# Sensor_Brushless_Driver_V1_01.net
KiCad netlist of a schematic drawn in Altium Designer
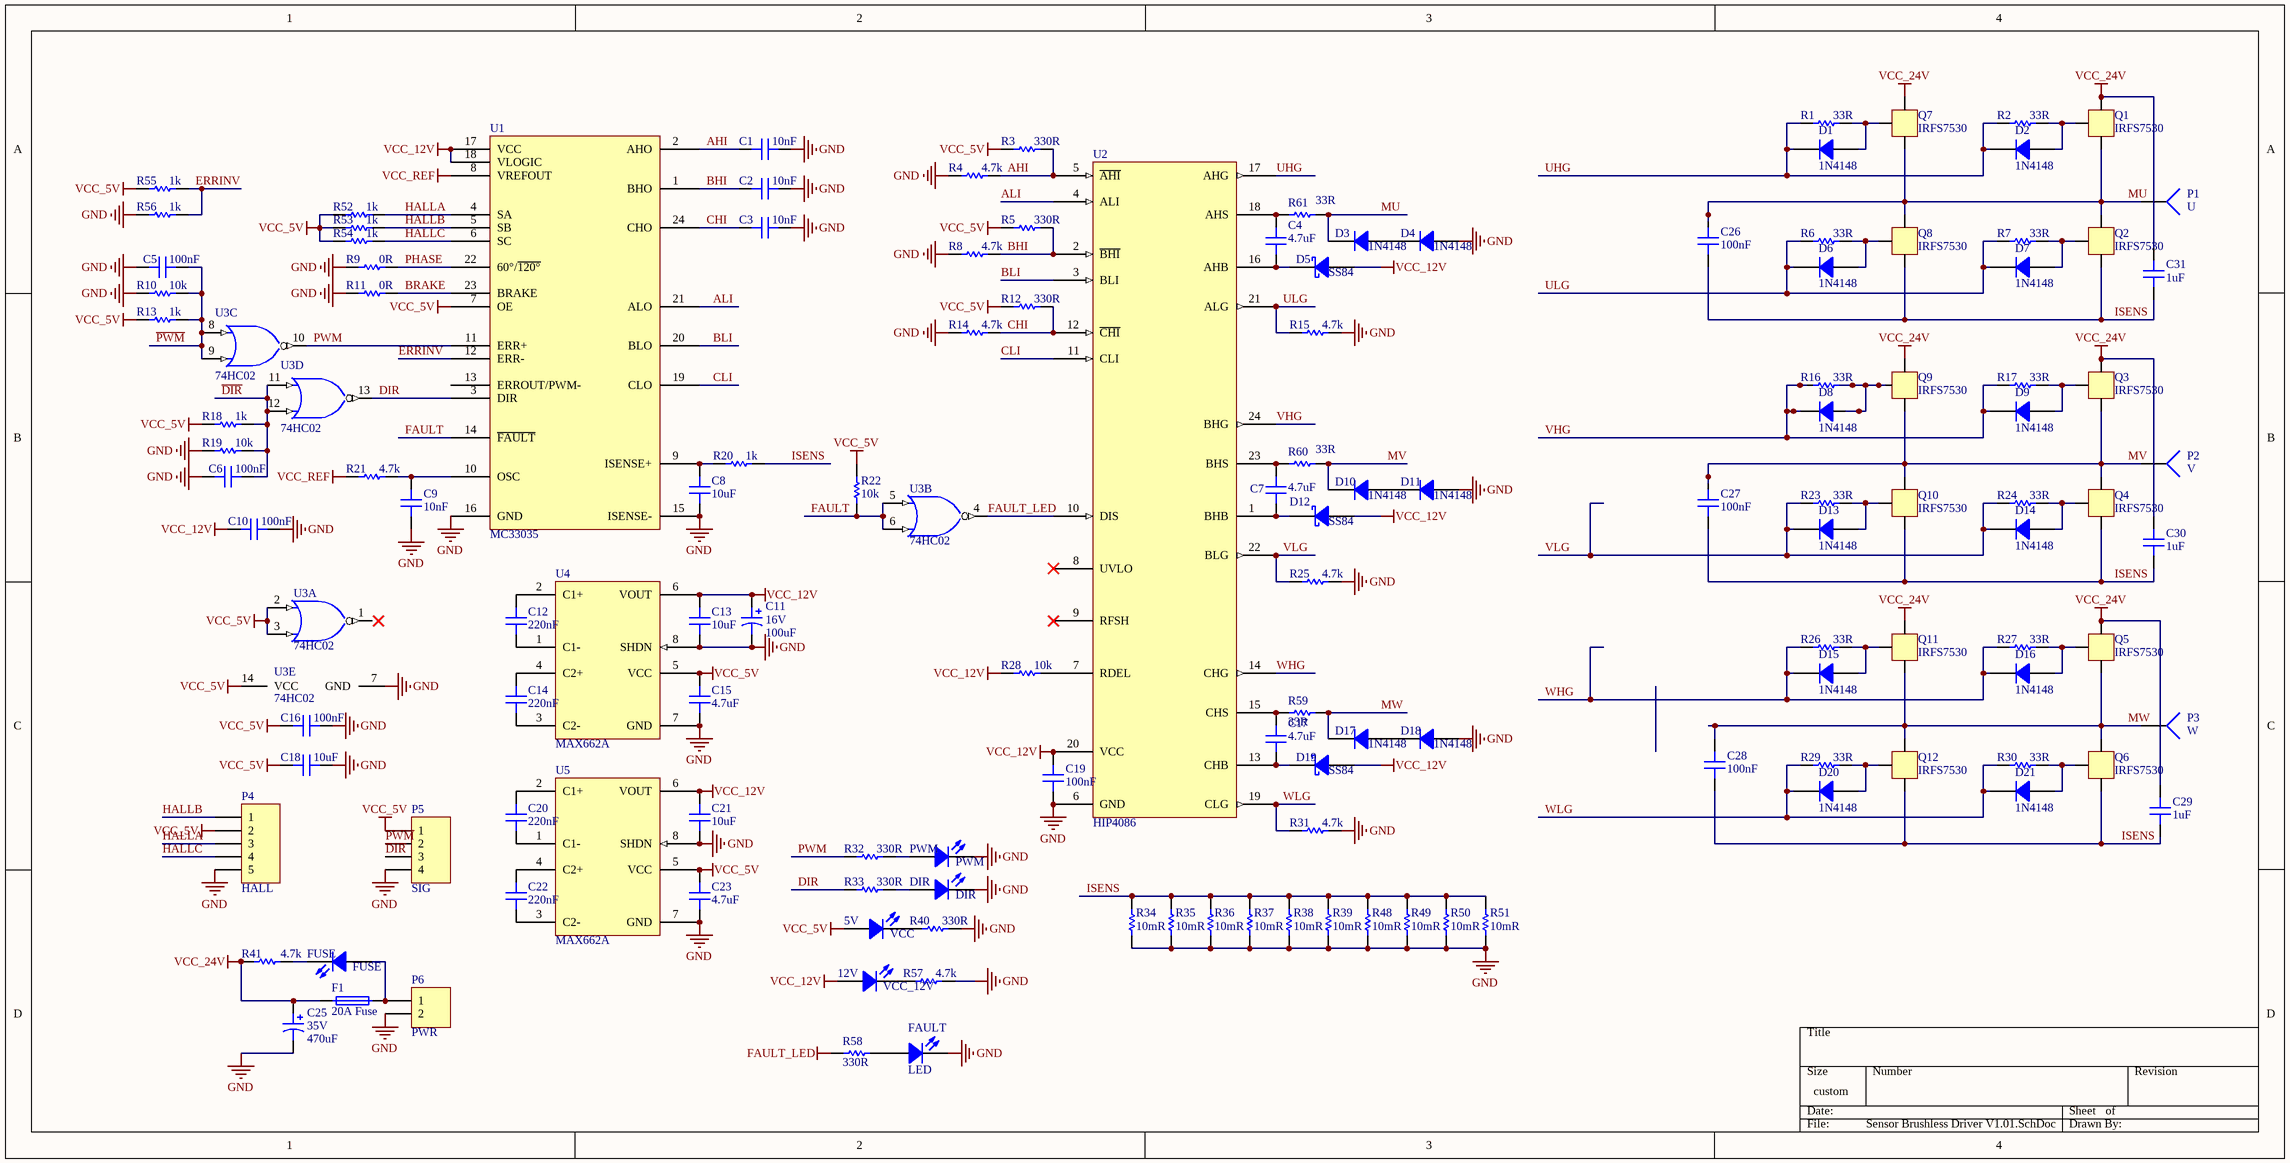
[diagram p0: Sensor Brushless Driver V1.01.SchDoc]

(export (version "E")
  (design (tool "Eeschema 10.0.6"))
  (components
    (comp (ref "5V")
      (value "VCC")
      (footprint "D0805")
      (description "Typical RED GaAs LED")
      (libsource (lib "Robocon_BJT") (part "LED"))
    )
    (comp (ref "12V")
      (value "VCC_12V")
      (footprint "D0805")
      (description "Typical RED GaAs LED")
      (libsource (lib "Robocon_BJT") (part "LED"))
    )
    (comp (ref "C1")
      (value "10nF")
      (footprint "CC2012-0805")
      (description "Capacitor (Semiconductor SIM Model)")
      (libsource (lib "Robocon_RCL") (part "Cap Semi"))
    )
    (comp (ref "C2")
      (value "10nF")
      (footprint "CC2012-0805")
      (description "Capacitor (Semiconductor SIM Model)")
      (libsource (lib "Robocon_RCL") (part "Cap Semi"))
    )
    (comp (ref "C3")
      (value "10nF")
      (footprint "CC2012-0805")
      (description "Capacitor (Semiconductor SIM Model)")
      (libsource (lib "Robocon_RCL") (part "Cap Semi"))
    )
    (comp (ref "C4")
      (value "4.7uF")
      (footprint "CC2012-0805")
      (description "Capacitor (Semiconductor SIM Model)")
      (libsource (lib "Robocon_RCL") (part "Cap Semi"))
    )
    (comp (ref "C5")
      (value "100nF")
      (footprint "CC2012-0805")
      (description "Capacitor (Semiconductor SIM Model)")
      (libsource (lib "Robocon_RCL") (part "Cap Semi"))
    )
    (comp (ref "C6")
      (value "100nF")
      (footprint "CC2012-0805")
      (description "Capacitor (Semiconductor SIM Model)")
      (libsource (lib "Robocon_RCL") (part "Cap Semi"))
    )
    (comp (ref "C7")
      (value "4.7uF")
      (footprint "CC2012-0805")
      (description "Capacitor (Semiconductor SIM Model)")
      (libsource (lib "Robocon_RCL") (part "Cap Semi"))
    )
    (comp (ref "C8")
      (value "10uF")
      (footprint "CC3216-1206")
      (description "Capacitor (Semiconductor SIM Model)")
      (libsource (lib "Robocon_RCL") (part "Cap Semi"))
    )
    (comp (ref "C9")
      (value "10nF")
      (footprint "CC2012-0805")
      (description "Capacitor (Semiconductor SIM Model)")
      (libsource (lib "Robocon_RCL") (part "Cap Semi"))
    )
    (comp (ref "C10")
      (value "100nF")
      (footprint "CC2012-0805")
      (description "Capacitor (Semiconductor SIM Model)")
      (libsource (lib "Robocon_RCL") (part "Cap Semi"))
    )
    (comp (ref "C11")
      (value "100uF")
      (footprint "EIA7343")
      (description "Polarized Capacitor (Axial)")
      (fields (field (name "VOLTAGE") "16V"))
      (libsource (lib "Robocon_RCL") (part "Cap Pol SMD"))
    )
    (comp (ref "C12")
      (value "220nF")
      (footprint "CC2012-0805")
      (description "Capacitor (Semiconductor SIM Model)")
      (libsource (lib "Robocon_RCL") (part "Cap Semi"))
    )
    (comp (ref "C13")
      (value "10uF")
      (footprint "CC3216-1206")
      (description "Capacitor (Semiconductor SIM Model)")
      (libsource (lib "Robocon_RCL") (part "Cap Semi"))
    )
    (comp (ref "C14")
      (value "220nF")
      (footprint "CC2012-0805")
      (description "Capacitor (Semiconductor SIM Model)")
      (libsource (lib "Robocon_RCL") (part "Cap Semi"))
    )
    (comp (ref "C15")
      (value "4.7uF")
      (footprint "CC2012-0805")
      (description "Capacitor (Semiconductor SIM Model)")
      (libsource (lib "Robocon_RCL") (part "Cap Semi"))
    )
    (comp (ref "C16")
      (value "100nF")
      (footprint "CC2012-0805")
      (description "Capacitor (Semiconductor SIM Model)")
      (libsource (lib "Robocon_RCL") (part "Cap Semi"))
    )
    (comp (ref "C17")
      (value "4.7uF")
      (footprint "CC2012-0805")
      (description "Capacitor (Semiconductor SIM Model)")
      (libsource (lib "Robocon_RCL") (part "Cap Semi"))
    )
    (comp (ref "C18")
      (value "10uF")
      (footprint "CC3216-1206")
      (description "Capacitor (Semiconductor SIM Model)")
      (libsource (lib "Robocon_RCL") (part "Cap Semi"))
    )
    (comp (ref "C19")
      (value "100nF")
      (footprint "CC2012-0805")
      (description "Capacitor (Semiconductor SIM Model)")
      (libsource (lib "Robocon_RCL") (part "Cap Semi"))
    )
    (comp (ref "C20")
      (value "220nF")
      (footprint "CC2012-0805")
      (description "Capacitor (Semiconductor SIM Model)")
      (libsource (lib "Robocon_RCL") (part "Cap Semi"))
    )
    (comp (ref "C21")
      (value "10uF")
      (footprint "CC3216-1206")
      (description "Capacitor (Semiconductor SIM Model)")
      (libsource (lib "Robocon_RCL") (part "Cap Semi"))
    )
    (comp (ref "C22")
      (value "220nF")
      (footprint "CC2012-0805")
      (description "Capacitor (Semiconductor SIM Model)")
      (libsource (lib "Robocon_RCL") (part "Cap Semi"))
    )
    (comp (ref "C23")
      (value "4.7uF")
      (footprint "CC2012-0805")
      (description "Capacitor (Semiconductor SIM Model)")
      (libsource (lib "Robocon_RCL") (part "Cap Semi"))
    )
    (comp (ref "C25")
      (value "470uF")
      (footprint "CAP10x12")
      (description "Polarized Capacitor (Radial)")
      (fields (field (name "VOLTAGE") "35V"))
      (libsource (lib "Robocon_RCL") (part "Cap Pol DIP"))
    )
    (comp (ref "C26")
      (value "100nF")
      (footprint "CC2012-0805")
      (description "Capacitor (Semiconductor SIM Model)")
      (libsource (lib "Robocon_RCL") (part "Cap Semi"))
    )
    (comp (ref "C27")
      (value "100nF")
      (footprint "CC2012-0805")
      (description "Capacitor (Semiconductor SIM Model)")
      (libsource (lib "Robocon_RCL") (part "Cap Semi"))
    )
    (comp (ref "C28")
      (value "100nF")
      (footprint "CC2012-0805")
      (description "Capacitor (Semiconductor SIM Model)")
      (libsource (lib "Robocon_RCL") (part "Cap Semi"))
    )
    (comp (ref "C29")
      (value "1uF")
      (footprint "CC2012-0805")
      (description "Capacitor (Semiconductor SIM Model)")
      (libsource (lib "Robocon_RCL") (part "Cap Semi"))
    )
    (comp (ref "C30")
      (value "1uF")
      (footprint "CC2012-0805")
      (description "Capacitor (Semiconductor SIM Model)")
      (libsource (lib "Robocon_RCL") (part "Cap Semi"))
    )
    (comp (ref "C31")
      (value "1uF")
      (footprint "CC2012-0805")
      (description "Capacitor (Semiconductor SIM Model)")
      (libsource (lib "Robocon_RCL") (part "Cap Semi"))
    )
    (comp (ref "D1")
      (value "1N4148")
      (footprint "SOD-80")
      (description "General Purpose Diode")
      (libsource (lib "Robocon_BJT") (part "D General"))
    )
    (comp (ref "D2")
      (value "1N4148")
      (footprint "SOD-80")
      (description "General Purpose Diode")
      (libsource (lib "Robocon_BJT") (part "D General"))
    )
    (comp (ref "D3")
      (value "1N4148")
      (footprint "SOD-80")
      (description "General Purpose Diode")
      (libsource (lib "Robocon_BJT") (part "D General"))
    )
    (comp (ref "D4")
      (value "1N4148")
      (footprint "SOD-80")
      (description "General Purpose Diode")
      (libsource (lib "Robocon_BJT") (part "D General"))
    )
    (comp (ref "D5")
      (value "SS84")
      (footprint "SMC")
      (description "Schottky Diode")
      (libsource (lib "Robocon_BJT") (part "D Schottky"))
    )
    (comp (ref "D6")
      (value "1N4148")
      (footprint "SOD-80")
      (description "General Purpose Diode")
      (libsource (lib "Robocon_BJT") (part "D General"))
    )
    (comp (ref "D7")
      (value "1N4148")
      (footprint "SOD-80")
      (description "General Purpose Diode")
      (libsource (lib "Robocon_BJT") (part "D General"))
    )
    (comp (ref "D8")
      (value "1N4148")
      (footprint "SOD-80")
      (description "General Purpose Diode")
      (libsource (lib "Robocon_BJT") (part "D General"))
    )
    (comp (ref "D9")
      (value "1N4148")
      (footprint "SOD-80")
      (description "General Purpose Diode")
      (libsource (lib "Robocon_BJT") (part "D General"))
    )
    (comp (ref "D10")
      (value "1N4148")
      (footprint "SOD-80")
      (description "General Purpose Diode")
      (libsource (lib "Robocon_BJT") (part "D General"))
    )
    (comp (ref "D11")
      (value "1N4148")
      (footprint "SOD-80")
      (description "General Purpose Diode")
      (libsource (lib "Robocon_BJT") (part "D General"))
    )
    (comp (ref "D12")
      (value "SS84")
      (footprint "SMC")
      (description "Schottky Diode")
      (libsource (lib "Robocon_BJT") (part "D Schottky"))
    )
    (comp (ref "D13")
      (value "1N4148")
      (footprint "SOD-80")
      (description "General Purpose Diode")
      (libsource (lib "Robocon_BJT") (part "D General"))
    )
    (comp (ref "D14")
      (value "1N4148")
      (footprint "SOD-80")
      (description "General Purpose Diode")
      (libsource (lib "Robocon_BJT") (part "D General"))
    )
    (comp (ref "D15")
      (value "1N4148")
      (footprint "SOD-80")
      (description "General Purpose Diode")
      (libsource (lib "Robocon_BJT") (part "D General"))
    )
    (comp (ref "D16")
      (value "1N4148")
      (footprint "SOD-80")
      (description "General Purpose Diode")
      (libsource (lib "Robocon_BJT") (part "D General"))
    )
    (comp (ref "D17")
      (value "1N4148")
      (footprint "SOD-80")
      (description "General Purpose Diode")
      (libsource (lib "Robocon_BJT") (part "D General"))
    )
    (comp (ref "D18")
      (value "1N4148")
      (footprint "SOD-80")
      (description "General Purpose Diode")
      (libsource (lib "Robocon_BJT") (part "D General"))
    )
    (comp (ref "D19")
      (value "SS84")
      (footprint "SMC")
      (description "Schottky Diode")
      (libsource (lib "Robocon_BJT") (part "D Schottky"))
    )
    (comp (ref "D20")
      (value "1N4148")
      (footprint "SOD-80")
      (description "General Purpose Diode")
      (libsource (lib "Robocon_BJT") (part "D General"))
    )
    (comp (ref "D21")
      (value "1N4148")
      (footprint "SOD-80")
      (description "General Purpose Diode")
      (libsource (lib "Robocon_BJT") (part "D General"))
    )
    (comp (ref "DIR")
      (value "DIR")
      (footprint "D0805")
      (description "Typical RED GaAs LED")
      (libsource (lib "Robocon_BJT") (part "LED"))
    )
    (comp (ref "F1")
      (value "20A Fuse")
      (footprint "Robocon_RCL:FUSE SOCKET")
      (description "Fuse")
      (libsource (lib "Robocon_RCL") (part "Fuse"))
    )
    (comp (ref "FAULT")
      (value "LED")
      (footprint "D0805")
      (description "Typical RED GaAs LED")
      (libsource (lib "Robocon_BJT") (part "LED"))
    )
    (comp (ref "FUSE")
      (value "FUSE")
      (footprint "D0805")
      (description "Typical RED GaAs LED")
      (libsource (lib "Robocon_BJT") (part "LED"))
    )
    (comp (ref "P1")
      (value "U")
      (footprint "2.5X4_WIRE_PAD")
      (description "Socket")
      (libsource (lib "Robocon_connectors") (part "Socket"))
    )
    (comp (ref "P2")
      (value "V")
      (footprint "2.5X4_WIRE_PAD")
      (description "Socket")
      (libsource (lib "Robocon_connectors") (part "Socket"))
    )
    (comp (ref "P3")
      (value "W")
      (footprint "2.5X4_WIRE_PAD")
      (description "Socket")
      (libsource (lib "Robocon_connectors") (part "Socket"))
    )
    (comp (ref "P4")
      (value "HALL")
      (footprint "LOCKEDHDR-5W")
      (description "Header, 5-Pin")
      (libsource (lib "Robocon_connectors") (part "Header 5"))
    )
    (comp (ref "P5")
      (value "SIG")
      (footprint "LOCKEDHDR-4W")
      (description "Header, 4-Pin")
      (libsource (lib "Robocon_connectors") (part "Header 4"))
    )
    (comp (ref "P6")
      (value "PWR")
      (footprint "xt60(m)")
      (description "Header, 2-Pin")
      (libsource (lib "Robocon_connectors") (part "Header 2"))
    )
    (comp (ref "PWM")
      (value "PWM")
      (footprint "D0805")
      (description "Typical RED GaAs LED")
      (libsource (lib "Robocon_BJT") (part "LED"))
    )
    (comp (ref "Q1") (value "IRFS7530") (footprint "D2k 7 pin") (libsource (lib "Schlib1") (part "D2k 7")))
    (comp (ref "Q2") (value "IRFS7530") (footprint "D2k 7 pin") (libsource (lib "Schlib1") (part "D2k 7")))
    (comp (ref "Q3") (value "IRFS7530") (footprint "D2k 7 pin") (libsource (lib "Schlib1") (part "D2k 7")))
    (comp (ref "Q4") (value "IRFS7530") (footprint "D2k 7 pin") (libsource (lib "Schlib1") (part "D2k 7")))
    (comp (ref "Q5") (value "IRFS7530") (footprint "D2k 7 pin") (libsource (lib "Schlib1") (part "D2k 7")))
    (comp (ref "Q6") (value "IRFS7530") (footprint "D2k 7 pin") (libsource (lib "Schlib1") (part "D2k 7")))
    (comp (ref "Q7") (value "IRFS7530") (footprint "D2k 7 pin") (libsource (lib "Schlib1") (part "D2k 7")))
    (comp (ref "Q8") (value "IRFS7530") (footprint "D2k 7 pin") (libsource (lib "Schlib1") (part "D2k 7")))
    (comp (ref "Q9") (value "IRFS7530") (footprint "D2k 7 pin") (libsource (lib "Schlib1") (part "D2k 7")))
    (comp (ref "Q10") (value "IRFS7530") (footprint "D2k 7 pin") (libsource (lib "Schlib1") (part "D2k 7")))
    (comp (ref "Q11") (value "IRFS7530") (footprint "D2k 7 pin") (libsource (lib "Schlib1") (part "D2k 7")))
    (comp (ref "Q12") (value "IRFS7530") (footprint "D2k 7 pin") (libsource (lib "Schlib1") (part "D2k 7")))
    (comp (ref "R1")
      (value "33R")
      (footprint "CR2012-0805")
      (description "Semiconductor Resistor")
      (libsource (lib "Robocon_RCL") (part "Res Semi"))
    )
    (comp (ref "R2")
      (value "33R")
      (footprint "CR2012-0805")
      (description "Semiconductor Resistor")
      (libsource (lib "Robocon_RCL") (part "Res Semi"))
    )
    (comp (ref "R3")
      (value "330R")
      (footprint "CR2012-0805")
      (description "Semiconductor Resistor")
      (libsource (lib "Robocon_RCL") (part "Res Semi"))
    )
    (comp (ref "R4")
      (value "4.7k")
      (footprint "CR2012-0805")
      (description "Semiconductor Resistor")
      (libsource (lib "Robocon_RCL") (part "Res Semi"))
    )
    (comp (ref "R5")
      (value "330R")
      (footprint "CR2012-0805")
      (description "Semiconductor Resistor")
      (libsource (lib "Robocon_RCL") (part "Res Semi"))
    )
    (comp (ref "R6")
      (value "33R")
      (footprint "CR2012-0805")
      (description "Semiconductor Resistor")
      (libsource (lib "Robocon_RCL") (part "Res Semi"))
    )
    (comp (ref "R7")
      (value "33R")
      (footprint "CR2012-0805")
      (description "Semiconductor Resistor")
      (libsource (lib "Robocon_RCL") (part "Res Semi"))
    )
    (comp (ref "R8")
      (value "4.7k")
      (footprint "CR2012-0805")
      (description "Semiconductor Resistor")
      (libsource (lib "Robocon_RCL") (part "Res Semi"))
    )
    (comp (ref "R9")
      (value "0R")
      (footprint "CR2012-0805")
      (description "Semiconductor Resistor")
      (libsource (lib "Robocon_RCL") (part "Res Semi"))
    )
    (comp (ref "R10")
      (value "10k")
      (footprint "CR2012-0805")
      (description "Semiconductor Resistor")
      (libsource (lib "Robocon_RCL") (part "Res Semi"))
    )
    (comp (ref "R11")
      (value "0R")
      (footprint "CR2012-0805")
      (description "Semiconductor Resistor")
      (libsource (lib "Robocon_RCL") (part "Res Semi"))
    )
    (comp (ref "R12")
      (value "330R")
      (footprint "CR2012-0805")
      (description "Semiconductor Resistor")
      (libsource (lib "Robocon_RCL") (part "Res Semi"))
    )
    (comp (ref "R13")
      (value "1k")
      (footprint "CR2012-0805")
      (description "Semiconductor Resistor")
      (libsource (lib "Robocon_RCL") (part "Res Semi"))
    )
    (comp (ref "R14")
      (value "4.7k")
      (footprint "CR2012-0805")
      (description "Semiconductor Resistor")
      (libsource (lib "Robocon_RCL") (part "Res Semi"))
    )
    (comp (ref "R15")
      (value "4.7k")
      (footprint "CR2012-0805")
      (description "Semiconductor Resistor")
      (libsource (lib "Robocon_RCL") (part "Res Semi"))
    )
    (comp (ref "R16")
      (value "33R")
      (footprint "CR2012-0805")
      (description "Semiconductor Resistor")
      (libsource (lib "Robocon_RCL") (part "Res Semi"))
    )
    (comp (ref "R17")
      (value "33R")
      (footprint "CR2012-0805")
      (description "Semiconductor Resistor")
      (libsource (lib "Robocon_RCL") (part "Res Semi"))
    )
    (comp (ref "R18")
      (value "1k")
      (footprint "CR2012-0805")
      (description "Semiconductor Resistor")
      (libsource (lib "Robocon_RCL") (part "Res Semi"))
    )
    (comp (ref "R19")
      (value "10k")
      (footprint "CR2012-0805")
      (description "Semiconductor Resistor")
      (libsource (lib "Robocon_RCL") (part "Res Semi"))
    )
    (comp (ref "R20")
      (value "1k")
      (footprint "CR2012-0805")
      (description "Semiconductor Resistor")
      (libsource (lib "Robocon_RCL") (part "Res Semi"))
    )
    (comp (ref "R21")
      (value "4.7k")
      (footprint "CR2012-0805")
      (description "Semiconductor Resistor")
      (libsource (lib "Robocon_RCL") (part "Res Semi"))
    )
    (comp (ref "R22")
      (value "10k")
      (footprint "CR2012-0805")
      (description "Semiconductor Resistor")
      (libsource (lib "Robocon_RCL") (part "Res Semi"))
    )
    (comp (ref "R23")
      (value "33R")
      (footprint "CR2012-0805")
      (description "Semiconductor Resistor")
      (libsource (lib "Robocon_RCL") (part "Res Semi"))
    )
    (comp (ref "R24")
      (value "33R")
      (footprint "CR2012-0805")
      (description "Semiconductor Resistor")
      (libsource (lib "Robocon_RCL") (part "Res Semi"))
    )
    (comp (ref "R25")
      (value "4.7k")
      (footprint "CR2012-0805")
      (description "Semiconductor Resistor")
      (libsource (lib "Robocon_RCL") (part "Res Semi"))
    )
    (comp (ref "R26")
      (value "33R")
      (footprint "CR2012-0805")
      (description "Semiconductor Resistor")
      (libsource (lib "Robocon_RCL") (part "Res Semi"))
    )
    (comp (ref "R27")
      (value "33R")
      (footprint "CR2012-0805")
      (description "Semiconductor Resistor")
      (libsource (lib "Robocon_RCL") (part "Res Semi"))
    )
    (comp (ref "R28")
      (value "10k")
      (footprint "CR2012-0805")
      (description "Semiconductor Resistor")
      (libsource (lib "Robocon_RCL") (part "Res Semi"))
    )
    (comp (ref "R29")
      (value "33R")
      (footprint "CR2012-0805")
      (description "Semiconductor Resistor")
      (libsource (lib "Robocon_RCL") (part "Res Semi"))
    )
    (comp (ref "R30")
      (value "33R")
      (footprint "CR2012-0805")
      (description "Semiconductor Resistor")
      (libsource (lib "Robocon_RCL") (part "Res Semi"))
    )
    (comp (ref "R31")
      (value "4.7k")
      (footprint "CR2012-0805")
      (description "Semiconductor Resistor")
      (libsource (lib "Robocon_RCL") (part "Res Semi"))
    )
    (comp (ref "R32")
      (value "330R")
      (footprint "CR2012-0805")
      (description "Semiconductor Resistor")
      (libsource (lib "Robocon_RCL") (part "Res Semi"))
    )
    (comp (ref "R33")
      (value "330R")
      (footprint "CR2012-0805")
      (description "Semiconductor Resistor")
      (libsource (lib "Robocon_RCL") (part "Res Semi"))
    )
    (comp (ref "R34")
      (value "10mR")
      (footprint "CR6332-2512")
      (description "Semiconductor Resistor")
      (libsource (lib "Robocon_RCL") (part "Res Semi"))
    )
    (comp (ref "R35")
      (value "10mR")
      (footprint "CR6332-2512")
      (description "Semiconductor Resistor")
      (libsource (lib "Robocon_RCL") (part "Res Semi"))
    )
    (comp (ref "R36")
      (value "10mR")
      (footprint "CR6332-2512")
      (description "Semiconductor Resistor")
      (libsource (lib "Robocon_RCL") (part "Res Semi"))
    )
    (comp (ref "R37")
      (value "10mR")
      (footprint "CR6332-2512")
      (description "Semiconductor Resistor")
      (libsource (lib "Robocon_RCL") (part "Res Semi"))
    )
    (comp (ref "R38")
      (value "10mR")
      (footprint "CR6332-2512")
      (description "Semiconductor Resistor")
      (libsource (lib "Robocon_RCL") (part "Res Semi"))
    )
    (comp (ref "R39")
      (value "10mR")
      (footprint "CR6332-2512")
      (description "Semiconductor Resistor")
      (libsource (lib "Robocon_RCL") (part "Res Semi"))
    )
    (comp (ref "R40")
      (value "330R")
      (footprint "CR2012-0805")
      (description "Semiconductor Resistor")
      (libsource (lib "Robocon_RCL") (part "Res Semi"))
    )
    (comp (ref "R41")
      (value "4.7k")
      (footprint "CR2012-0805")
      (description "Semiconductor Resistor")
      (libsource (lib "Robocon_RCL") (part "Res Semi"))
    )
    (comp (ref "R48")
      (value "10mR")
      (footprint "CR6332-2512")
      (description "Semiconductor Resistor")
      (libsource (lib "Robocon_RCL") (part "Res Semi"))
    )
    (comp (ref "R49")
      (value "10mR")
      (footprint "CR6332-2512")
      (description "Semiconductor Resistor")
      (libsource (lib "Robocon_RCL") (part "Res Semi"))
    )
    (comp (ref "R50")
      (value "10mR")
      (footprint "CR6332-2512")
      (description "Semiconductor Resistor")
      (libsource (lib "Robocon_RCL") (part "Res Semi"))
    )
    (comp (ref "R51")
      (value "10mR")
      (footprint "CR6332-2512")
      (description "Semiconductor Resistor")
      (libsource (lib "Robocon_RCL") (part "Res Semi"))
    )
    (comp (ref "R52")
      (value "1k")
      (footprint "CR2012-0805")
      (description "Semiconductor Resistor")
      (libsource (lib "Robocon_RCL") (part "Res Semi"))
    )
    (comp (ref "R53")
      (value "1k")
      (footprint "CR2012-0805")
      (description "Semiconductor Resistor")
      (libsource (lib "Robocon_RCL") (part "Res Semi"))
    )
    (comp (ref "R54")
      (value "1k")
      (footprint "CR2012-0805")
      (description "Semiconductor Resistor")
      (libsource (lib "Robocon_RCL") (part "Res Semi"))
    )
    (comp (ref "R55")
      (value "1k")
      (footprint "CR2012-0805")
      (description "Semiconductor Resistor")
      (libsource (lib "Robocon_RCL") (part "Res Semi"))
    )
    (comp (ref "R56")
      (value "1k")
      (footprint "CR2012-0805")
      (description "Semiconductor Resistor")
      (libsource (lib "Robocon_RCL") (part "Res Semi"))
    )
    (comp (ref "R57")
      (value "4.7k")
      (footprint "CR2012-0805")
      (description "Semiconductor Resistor")
      (libsource (lib "Robocon_RCL") (part "Res Semi"))
    )
    (comp (ref "R58")
      (value "330R")
      (footprint "CR2012-0805")
      (description "Semiconductor Resistor")
      (libsource (lib "Robocon_RCL") (part "Res Semi"))
    )
    (comp (ref "R59")
      (value "33R")
      (footprint "CR2012-0805")
      (description "Semiconductor Resistor")
      (libsource (lib "Robocon_RCL") (part "Res Semi"))
    )
    (comp (ref "R60")
      (value "33R")
      (footprint "CR2012-0805")
      (description "Semiconductor Resistor")
      (libsource (lib "Robocon_RCL") (part "Res Semi"))
    )
    (comp (ref "R61")
      (value "33R")
      (footprint "CR2012-0805")
      (description "Semiconductor Resistor")
      (libsource (lib "Robocon_RCL") (part "Res Semi"))
    )
    (comp (ref "U1")
      (value "MC33035")
      (footprint "SOP-24")
      (description "80V/2.5A Peak, High Frequency Full\r\nBridge FET Driver")
      (libsource (lib "Robocon_IC") (part "MC33035"))
    )
    (comp (ref "U2")
      (value "HIP4086")
      (footprint "SOP-24")
      (description "80V, 500mA, 3-Phase MOSFET Driver80V, 500mA, 3-Phase MOSFET Driver")
      (libsource (lib "Robocon_IC") (part "HIP4086"))
    )
    (comp (ref "U3")
      (value "74HC02")
      (footprint "SOP-14")
      (description "Quadruple 2-Input Positive-NOR Gate")
      (libsource (lib "Robocon_IC") (part "74HC02"))
    )
    (comp (ref "U4")
      (value "MAX662A")
      (footprint "SOP-8")
      (description "5V to 12V Charge Pump")
      (libsource (lib "Robocon_IC") (part "MAX662A"))
    )
    (comp (ref "U5")
      (value "MAX662A")
      (footprint "SOP-8")
      (description "5V to 12V Charge Pump")
      (libsource (lib "Robocon_IC") (part "MAX662A"))
    )
  )
  (nets
    (net (code "1") (name "/AHI") (class "Default")
      (node (ref "C1") (pin "2") (pinfunction "2_2") (pintype "passive"))
      (node (ref "R3") (pin "1") (pinfunction "1_1") (pintype "passive"))
      (node (ref "R4") (pin "1") (pinfunction "1_1") (pintype "passive"))
      (node (ref "U1") (pin "2") (pinfunction "AHO_2") (pintype "passive"))
      (node (ref "U2") (pin "5") (pinfunction "~{AHI}_5") (pintype "input"))
    )
    (net (code "2") (name "/ALI") (class "Default")
      (node (ref "U1") (pin "21") (pinfunction "ALO_21") (pintype "passive"))
      (node (ref "U2") (pin "4") (pinfunction "ALI_4") (pintype "input"))
    )
    (net (code "3") (name "/BHI") (class "Default")
      (node (ref "C2") (pin "2") (pinfunction "2_2") (pintype "passive"))
      (node (ref "R5") (pin "1") (pinfunction "1_1") (pintype "passive"))
      (node (ref "R8") (pin "1") (pinfunction "1_1") (pintype "passive"))
      (node (ref "U1") (pin "1") (pinfunction "BHO_1") (pintype "passive"))
      (node (ref "U2") (pin "2") (pinfunction "~{BHI}_2") (pintype "input"))
    )
    (net (code "4") (name "/BLI") (class "Default")
      (node (ref "U1") (pin "20") (pinfunction "BLO_20") (pintype "passive"))
      (node (ref "U2") (pin "3") (pinfunction "BLI_3") (pintype "input"))
    )
    (net (code "5") (name "/BRAKE") (class "Default")
      (node (ref "R11") (pin "1") (pinfunction "1_1") (pintype "passive"))
      (node (ref "U1") (pin "23") (pinfunction "BRAKE_23") (pintype "passive"))
    )
    (net (code "6") (name "/CHI") (class "Default")
      (node (ref "C3") (pin "2") (pinfunction "2_2") (pintype "passive"))
      (node (ref "R12") (pin "1") (pinfunction "1_1") (pintype "passive"))
      (node (ref "R14") (pin "1") (pinfunction "1_1") (pintype "passive"))
      (node (ref "U1") (pin "24") (pinfunction "CHO_24") (pintype "passive"))
      (node (ref "U2") (pin "12") (pinfunction "~{CHI}_12") (pintype "input"))
    )
    (net (code "7") (name "/CLI") (class "Default")
      (node (ref "U1") (pin "19") (pinfunction "CLO_19") (pintype "passive"))
      (node (ref "U2") (pin "11") (pinfunction "CLI_11") (pintype "input"))
    )
    (net (code "8") (name "/DIR") (class "Default")
      (node (ref "R33") (pin "2") (pinfunction "2_2") (pintype "passive"))
      (node (ref "U1") (pin "3") (pinfunction "DIR_3") (pintype "passive"))
      (node (ref "U3") (pin "13") (pinfunction "4Y_13") (pintype "output"))
    )
    (net (code "9") (name "/ERRINV") (class "Default")
      (node (ref "R55") (pin "1") (pinfunction "1_1") (pintype "passive"))
      (node (ref "R56") (pin "1") (pinfunction "1_1") (pintype "passive"))
      (node (ref "U1") (pin "12") (pinfunction "ERR-_12") (pintype "passive"))
    )
    (net (code "10") (name "/FAULT") (class "Default")
      (node (ref "R22") (pin "1") (pinfunction "1_1") (pintype "passive"))
      (node (ref "U1") (pin "14") (pinfunction "~{FAULT}_14") (pintype "passive"))
      (node (ref "U3") (pin "5") (pinfunction "2A_5") (pintype "input"))
      (node (ref "U3") (pin "6") (pinfunction "2B_6") (pintype "input"))
    )
    (net (code "11") (name "/HALLA") (class "Default")
      (node (ref "P4") (pin "3") (pinfunction "3_3") (pintype "passive"))
      (node (ref "R52") (pin "1") (pinfunction "1_1") (pintype "passive"))
      (node (ref "U1") (pin "4") (pinfunction "SA_4") (pintype "passive"))
    )
    (net (code "12") (name "/HALLB") (class "Default")
      (node (ref "P4") (pin "1") (pinfunction "1_1") (pintype "passive"))
      (node (ref "R53") (pin "1") (pinfunction "1_1") (pintype "passive"))
      (node (ref "U1") (pin "5") (pinfunction "SB_5") (pintype "passive"))
    )
    (net (code "13") (name "/HALLC") (class "Default")
      (node (ref "P4") (pin "4") (pinfunction "4_4") (pintype "passive"))
      (node (ref "R54") (pin "1") (pinfunction "1_1") (pintype "passive"))
      (node (ref "U1") (pin "6") (pinfunction "SC_6") (pintype "passive"))
    )
    (net (code "14") (name "/ISENS") (class "Default")
      (node (ref "C26") (pin "1") (pinfunction "1_1") (pintype "passive"))
      (node (ref "C27") (pin "1") (pinfunction "1_1") (pintype "passive"))
      (node (ref "C28") (pin "1") (pinfunction "1_1") (pintype "passive"))
      (node (ref "C29") (pin "1") (pinfunction "1_1") (pintype "passive"))
      (node (ref "C30") (pin "1") (pinfunction "1_1") (pintype "passive"))
      (node (ref "C31") (pin "1") (pinfunction "1_1") (pintype "passive"))
      (node (ref "Q10") (pin "0") (pinfunction "S_0") (pintype "passive"))
      (node (ref "Q12") (pin "0") (pinfunction "S_0") (pintype "passive"))
      (node (ref "Q2") (pin "0") (pinfunction "S_0") (pintype "passive"))
      (node (ref "Q4") (pin "0") (pinfunction "S_0") (pintype "passive"))
      (node (ref "Q6") (pin "0") (pinfunction "S_0") (pintype "passive"))
      (node (ref "Q8") (pin "0") (pinfunction "S_0") (pintype "passive"))
      (node (ref "R20") (pin "1") (pinfunction "1_1") (pintype "passive"))
      (node (ref "R34") (pin "2") (pinfunction "2_2") (pintype "passive"))
      (node (ref "R35") (pin "2") (pinfunction "2_2") (pintype "passive"))
      (node (ref "R36") (pin "2") (pinfunction "2_2") (pintype "passive"))
      (node (ref "R37") (pin "2") (pinfunction "2_2") (pintype "passive"))
      (node (ref "R38") (pin "2") (pinfunction "2_2") (pintype "passive"))
      (node (ref "R39") (pin "2") (pinfunction "2_2") (pintype "passive"))
      (node (ref "R48") (pin "2") (pinfunction "2_2") (pintype "passive"))
      (node (ref "R49") (pin "2") (pinfunction "2_2") (pintype "passive"))
      (node (ref "R50") (pin "2") (pinfunction "2_2") (pintype "passive"))
      (node (ref "R51") (pin "2") (pinfunction "2_2") (pintype "passive"))
    )
    (net (code "15") (name "/MU") (class "Default")
      (node (ref "C26") (pin "2") (pinfunction "2_2") (pintype "passive"))
      (node (ref "D3") (pin "2") (pinfunction "K_2") (pintype "passive"))
      (node (ref "P1") (pin "1") (pinfunction "1_1") (pintype "passive"))
      (node (ref "Q1") (pin "0") (pinfunction "S_0") (pintype "passive"))
      (node (ref "Q2") (pin "2") (pinfunction "D_2") (pintype "passive"))
      (node (ref "Q7") (pin "0") (pinfunction "S_0") (pintype "passive"))
      (node (ref "Q8") (pin "2") (pinfunction "D_2") (pintype "passive"))
      (node (ref "R61") (pin "2") (pinfunction "2_2") (pintype "passive"))
    )
    (net (code "16") (name "/MV") (class "Default")
      (node (ref "C27") (pin "2") (pinfunction "2_2") (pintype "passive"))
      (node (ref "D10") (pin "2") (pinfunction "K_2") (pintype "passive"))
      (node (ref "P2") (pin "1") (pinfunction "1_1") (pintype "passive"))
      (node (ref "Q10") (pin "2") (pinfunction "D_2") (pintype "passive"))
      (node (ref "Q3") (pin "0") (pinfunction "S_0") (pintype "passive"))
      (node (ref "Q4") (pin "2") (pinfunction "D_2") (pintype "passive"))
      (node (ref "Q9") (pin "0") (pinfunction "S_0") (pintype "passive"))
      (node (ref "R60") (pin "2") (pinfunction "2_2") (pintype "passive"))
    )
    (net (code "17") (name "/MW") (class "Default")
      (node (ref "C28") (pin "2") (pinfunction "2_2") (pintype "passive"))
      (node (ref "D17") (pin "2") (pinfunction "K_2") (pintype "passive"))
      (node (ref "P3") (pin "1") (pinfunction "1_1") (pintype "passive"))
      (node (ref "Q11") (pin "0") (pinfunction "S_0") (pintype "passive"))
      (node (ref "Q12") (pin "2") (pinfunction "D_2") (pintype "passive"))
      (node (ref "Q5") (pin "0") (pinfunction "S_0") (pintype "passive"))
      (node (ref "Q6") (pin "2") (pinfunction "D_2") (pintype "passive"))
      (node (ref "R59") (pin "2") (pinfunction "2_2") (pintype "passive"))
    )
    (net (code "18") (name "/PHASE") (class "Default")
      (node (ref "R9") (pin "1") (pinfunction "1_1") (pintype "passive"))
      (node (ref "U1") (pin "22") (pinfunction "60°/~{120°}_22") (pintype "passive"))
    )
    (net (code "19") (name "/PWM") (class "Default")
      (node (ref "R32") (pin "2") (pinfunction "2_2") (pintype "passive"))
      (node (ref "U1") (pin "11") (pinfunction "ERR+_11") (pintype "passive"))
      (node (ref "U3") (pin "10") (pinfunction "3Y_10") (pintype "output"))
    )
    (net (code "20") (name "/UHG") (class "Default")
      (node (ref "D1") (pin "2") (pinfunction "K_2") (pintype "passive"))
      (node (ref "D2") (pin "2") (pinfunction "K_2") (pintype "passive"))
      (node (ref "R1") (pin "1") (pinfunction "1_1") (pintype "passive"))
      (node (ref "R2") (pin "1") (pinfunction "1_1") (pintype "passive"))
      (node (ref "U2") (pin "17") (pinfunction "AHG_17") (pintype "output"))
    )
    (net (code "21") (name "/ULG") (class "Default")
      (node (ref "D6") (pin "2") (pinfunction "K_2") (pintype "passive"))
      (node (ref "D7") (pin "2") (pinfunction "K_2") (pintype "passive"))
      (node (ref "R15") (pin "2") (pinfunction "2_2") (pintype "passive"))
      (node (ref "R6") (pin "1") (pinfunction "1_1") (pintype "passive"))
      (node (ref "R7") (pin "1") (pinfunction "1_1") (pintype "passive"))
      (node (ref "U2") (pin "21") (pinfunction "ALG_21") (pintype "output"))
    )
    (net (code "22") (name "/VHG") (class "Default")
      (node (ref "D8") (pin "2") (pinfunction "K_2") (pintype "passive"))
      (node (ref "D9") (pin "2") (pinfunction "K_2") (pintype "passive"))
      (node (ref "R16") (pin "1") (pinfunction "1_1") (pintype "passive"))
      (node (ref "R17") (pin "1") (pinfunction "1_1") (pintype "passive"))
      (node (ref "U2") (pin "24") (pinfunction "BHG_24") (pintype "output"))
    )
    (net (code "23") (name "/VLG") (class "Default")
      (node (ref "D13") (pin "2") (pinfunction "K_2") (pintype "passive"))
      (node (ref "D14") (pin "2") (pinfunction "K_2") (pintype "passive"))
      (node (ref "R23") (pin "1") (pinfunction "1_1") (pintype "passive"))
      (node (ref "R24") (pin "1") (pinfunction "1_1") (pintype "passive"))
      (node (ref "R25") (pin "2") (pinfunction "2_2") (pintype "passive"))
      (node (ref "U2") (pin "22") (pinfunction "BLG_22") (pintype "output"))
    )
    (net (code "24") (name "/WHG") (class "Default")
      (node (ref "D15") (pin "2") (pinfunction "K_2") (pintype "passive"))
      (node (ref "D16") (pin "2") (pinfunction "K_2") (pintype "passive"))
      (node (ref "R26") (pin "1") (pinfunction "1_1") (pintype "passive"))
      (node (ref "R27") (pin "1") (pinfunction "1_1") (pintype "passive"))
      (node (ref "U2") (pin "14") (pinfunction "CHG_14") (pintype "output"))
    )
    (net (code "25") (name "/WLG") (class "Default")
      (node (ref "D20") (pin "2") (pinfunction "K_2") (pintype "passive"))
      (node (ref "D21") (pin "2") (pinfunction "K_2") (pintype "passive"))
      (node (ref "R29") (pin "1") (pinfunction "1_1") (pintype "passive"))
      (node (ref "R30") (pin "1") (pinfunction "1_1") (pintype "passive"))
      (node (ref "R31") (pin "2") (pinfunction "2_2") (pintype "passive"))
      (node (ref "U2") (pin "19") (pinfunction "CLG_19") (pintype "output"))
    )
    (net (code "26") (name "/~{DIR}") (class "Default")
      (node (ref "C6") (pin "1") (pinfunction "1_1") (pintype "passive"))
      (node (ref "P5") (pin "3") (pinfunction "3_3") (pintype "passive"))
      (node (ref "R18") (pin "1") (pinfunction "1_1") (pintype "passive"))
      (node (ref "R19") (pin "1") (pinfunction "1_1") (pintype "passive"))
      (node (ref "U3") (pin "11") (pinfunction "4A_11") (pintype "input"))
      (node (ref "U3") (pin "12") (pinfunction "4B_12") (pintype "input"))
    )
    (net (code "27") (name "/~{PWM}") (class "Default")
      (node (ref "C5") (pin "1") (pinfunction "1_1") (pintype "passive"))
      (node (ref "P5") (pin "2") (pinfunction "2_2") (pintype "passive"))
      (node (ref "R10") (pin "1") (pinfunction "1_1") (pintype "passive"))
      (node (ref "R13") (pin "1") (pinfunction "1_1") (pintype "passive"))
      (node (ref "U3") (pin "8") (pinfunction "3A_8") (pintype "input"))
      (node (ref "U3") (pin "9") (pinfunction "3B_9") (pintype "input"))
    )
    (net (code "28") (name "FAULT_LED") (class "Default")
      (node (ref "R58") (pin "2") (pinfunction "2_2") (pintype "passive"))
      (node (ref "U2") (pin "10") (pinfunction "DIS_10") (pintype "input"))
      (node (ref "U3") (pin "4") (pinfunction "2Y_4") (pintype "output"))
    )
    (net (code "29") (name "GND") (class "Default")
      (node (ref "C1") (pin "1") (pinfunction "1_1") (pintype "passive"))
      (node (ref "C10") (pin "2") (pinfunction "2_2") (pintype "passive"))
      (node (ref "C11") (pin "2") (pinfunction "2_2") (pintype "passive"))
      (node (ref "C13") (pin "2") (pinfunction "2_2") (pintype "passive"))
      (node (ref "C15") (pin "2") (pinfunction "2_2") (pintype "passive"))
      (node (ref "C16") (pin "2") (pinfunction "2_2") (pintype "passive"))
      (node (ref "C18") (pin "2") (pinfunction "2_2") (pintype "passive"))
      (node (ref "C19") (pin "2") (pinfunction "2_2") (pintype "passive"))
      (node (ref "C2") (pin "1") (pinfunction "1_1") (pintype "passive"))
      (node (ref "C21") (pin "2") (pinfunction "2_2") (pintype "passive"))
      (node (ref "C23") (pin "2") (pinfunction "2_2") (pintype "passive"))
      (node (ref "C25") (pin "2") (pinfunction "2_2") (pintype "passive"))
      (node (ref "C3") (pin "1") (pinfunction "1_1") (pintype "passive"))
      (node (ref "C5") (pin "2") (pinfunction "2_2") (pintype "passive"))
      (node (ref "C6") (pin "2") (pinfunction "2_2") (pintype "passive"))
      (node (ref "C8") (pin "2") (pinfunction "2_2") (pintype "passive"))
      (node (ref "C9") (pin "2") (pinfunction "2_2") (pintype "passive"))
      (node (ref "D11") (pin "1") (pinfunction "A_1") (pintype "passive"))
      (node (ref "D18") (pin "1") (pinfunction "A_1") (pintype "passive"))
      (node (ref "D4") (pin "1") (pinfunction "A_1") (pintype "passive"))
      (node (ref "DIR") (pin "2") (pinfunction "K_2") (pintype "passive"))
      (node (ref "FAULT") (pin "2") (pinfunction "K_2") (pintype "passive"))
      (node (ref "P4") (pin "5") (pinfunction "5_5") (pintype "passive"))
      (node (ref "P5") (pin "4") (pinfunction "4_4") (pintype "passive"))
      (node (ref "P6") (pin "2") (pinfunction "2_2") (pintype "passive"))
      (node (ref "PWM") (pin "2") (pinfunction "K_2") (pintype "passive"))
      (node (ref "R10") (pin "2") (pinfunction "2_2") (pintype "passive"))
      (node (ref "R11") (pin "2") (pinfunction "2_2") (pintype "passive"))
      (node (ref "R14") (pin "2") (pinfunction "2_2") (pintype "passive"))
      (node (ref "R15") (pin "1") (pinfunction "1_1") (pintype "passive"))
      (node (ref "R19") (pin "2") (pinfunction "2_2") (pintype "passive"))
      (node (ref "R25") (pin "1") (pinfunction "1_1") (pintype "passive"))
      (node (ref "R31") (pin "1") (pinfunction "1_1") (pintype "passive"))
      (node (ref "R34") (pin "1") (pinfunction "1_1") (pintype "passive"))
      (node (ref "R35") (pin "1") (pinfunction "1_1") (pintype "passive"))
      (node (ref "R36") (pin "1") (pinfunction "1_1") (pintype "passive"))
      (node (ref "R37") (pin "1") (pinfunction "1_1") (pintype "passive"))
      (node (ref "R38") (pin "1") (pinfunction "1_1") (pintype "passive"))
      (node (ref "R39") (pin "1") (pinfunction "1_1") (pintype "passive"))
      (node (ref "R4") (pin "2") (pinfunction "2_2") (pintype "passive"))
      (node (ref "R40") (pin "1") (pinfunction "1_1") (pintype "passive"))
      (node (ref "R48") (pin "1") (pinfunction "1_1") (pintype "passive"))
      (node (ref "R49") (pin "1") (pinfunction "1_1") (pintype "passive"))
      (node (ref "R50") (pin "1") (pinfunction "1_1") (pintype "passive"))
      (node (ref "R51") (pin "1") (pinfunction "1_1") (pintype "passive"))
      (node (ref "R56") (pin "2") (pinfunction "2_2") (pintype "passive"))
      (node (ref "R57") (pin "1") (pinfunction "1_1") (pintype "passive"))
      (node (ref "R8") (pin "2") (pinfunction "2_2") (pintype "passive"))
      (node (ref "R9") (pin "2") (pinfunction "2_2") (pintype "passive"))
      (node (ref "U1") (pin "15") (pinfunction "ISENSE-_15") (pintype "passive"))
      (node (ref "U1") (pin "16") (pinfunction "GND_16") (pintype "passive"))
      (node (ref "U2") (pin "6") (pinfunction "GND_6") (pintype "passive"))
      (node (ref "U3") (pin "7") (pinfunction "GND_7") (pintype "power_in"))
      (node (ref "U4") (pin "7") (pinfunction "GND_7") (pintype "passive"))
      (node (ref "U4") (pin "8") (pinfunction "SHDN_8") (pintype "input"))
      (node (ref "U5") (pin "7") (pinfunction "GND_7") (pintype "passive"))
      (node (ref "U5") (pin "8") (pinfunction "SHDN_8") (pintype "input"))
    )
    (net (code "30") (name "Net-(5V-K)") (class "Default")
      (node (ref "5V") (pin "2") (pinfunction "K_2") (pintype "passive"))
      (node (ref "R40") (pin "2") (pinfunction "2_2") (pintype "passive"))
    )
    (net (code "31") (name "Net-(12V-K)") (class "Default")
      (node (ref "12V") (pin "2") (pinfunction "K_2") (pintype "passive"))
      (node (ref "R57") (pin "2") (pinfunction "2_2") (pintype "passive"))
    )
    (net (code "32") (name "Net-(D1-A)") (class "Default")
      (node (ref "D1") (pin "1") (pinfunction "A_1") (pintype "passive"))
      (node (ref "Q7") (pin "1") (pinfunction "1_1") (pintype "passive"))
      (node (ref "R1") (pin "2") (pinfunction "2_2") (pintype "passive"))
    )
    (net (code "33") (name "Net-(D2-A)") (class "Default")
      (node (ref "D2") (pin "1") (pinfunction "A_1") (pintype "passive"))
      (node (ref "Q1") (pin "1") (pinfunction "1_1") (pintype "passive"))
      (node (ref "R2") (pin "2") (pinfunction "2_2") (pintype "passive"))
    )
    (net (code "34") (name "Net-(D3-A)") (class "Default")
      (node (ref "D3") (pin "1") (pinfunction "A_1") (pintype "passive"))
      (node (ref "D4") (pin "2") (pinfunction "K_2") (pintype "passive"))
    )
    (net (code "35") (name "Net-(D5-K)") (class "Default")
      (node (ref "C4") (pin "1") (pinfunction "1_1") (pintype "passive"))
      (node (ref "D5") (pin "2") (pinfunction "K_2") (pintype "passive"))
      (node (ref "U2") (pin "16") (pinfunction "AHB_16") (pintype "passive"))
    )
    (net (code "36") (name "Net-(D6-A)") (class "Default")
      (node (ref "D6") (pin "1") (pinfunction "A_1") (pintype "passive"))
      (node (ref "Q8") (pin "1") (pinfunction "1_1") (pintype "passive"))
      (node (ref "R6") (pin "2") (pinfunction "2_2") (pintype "passive"))
    )
    (net (code "37") (name "Net-(D7-A)") (class "Default")
      (node (ref "D7") (pin "1") (pinfunction "A_1") (pintype "passive"))
      (node (ref "Q2") (pin "1") (pinfunction "1_1") (pintype "passive"))
      (node (ref "R7") (pin "2") (pinfunction "2_2") (pintype "passive"))
    )
    (net (code "38") (name "Net-(D8-A)") (class "Default")
      (node (ref "D8") (pin "1") (pinfunction "A_1") (pintype "passive"))
      (node (ref "Q9") (pin "1") (pinfunction "1_1") (pintype "passive"))
      (node (ref "R16") (pin "2") (pinfunction "2_2") (pintype "passive"))
    )
    (net (code "39") (name "Net-(D9-A)") (class "Default")
      (node (ref "D9") (pin "1") (pinfunction "A_1") (pintype "passive"))
      (node (ref "Q3") (pin "1") (pinfunction "1_1") (pintype "passive"))
      (node (ref "R17") (pin "2") (pinfunction "2_2") (pintype "passive"))
    )
    (net (code "40") (name "Net-(D10-A)") (class "Default")
      (node (ref "D10") (pin "1") (pinfunction "A_1") (pintype "passive"))
      (node (ref "D11") (pin "2") (pinfunction "K_2") (pintype "passive"))
    )
    (net (code "41") (name "Net-(D12-K)") (class "Default")
      (node (ref "C7") (pin "1") (pinfunction "1_1") (pintype "passive"))
      (node (ref "D12") (pin "2") (pinfunction "K_2") (pintype "passive"))
      (node (ref "U2") (pin "1") (pinfunction "BHB_1") (pintype "passive"))
    )
    (net (code "42") (name "Net-(D13-A)") (class "Default")
      (node (ref "D13") (pin "1") (pinfunction "A_1") (pintype "passive"))
      (node (ref "Q10") (pin "1") (pinfunction "1_1") (pintype "passive"))
      (node (ref "R23") (pin "2") (pinfunction "2_2") (pintype "passive"))
    )
    (net (code "43") (name "Net-(D14-A)") (class "Default")
      (node (ref "D14") (pin "1") (pinfunction "A_1") (pintype "passive"))
      (node (ref "Q4") (pin "1") (pinfunction "1_1") (pintype "passive"))
      (node (ref "R24") (pin "2") (pinfunction "2_2") (pintype "passive"))
    )
    (net (code "44") (name "Net-(D15-A)") (class "Default")
      (node (ref "D15") (pin "1") (pinfunction "A_1") (pintype "passive"))
      (node (ref "Q11") (pin "1") (pinfunction "1_1") (pintype "passive"))
      (node (ref "R26") (pin "2") (pinfunction "2_2") (pintype "passive"))
    )
    (net (code "45") (name "Net-(D16-A)") (class "Default")
      (node (ref "D16") (pin "1") (pinfunction "A_1") (pintype "passive"))
      (node (ref "Q5") (pin "1") (pinfunction "1_1") (pintype "passive"))
      (node (ref "R27") (pin "2") (pinfunction "2_2") (pintype "passive"))
    )
    (net (code "46") (name "Net-(D17-A)") (class "Default")
      (node (ref "D17") (pin "1") (pinfunction "A_1") (pintype "passive"))
      (node (ref "D18") (pin "2") (pinfunction "K_2") (pintype "passive"))
    )
    (net (code "47") (name "Net-(D19-K)") (class "Default")
      (node (ref "C17") (pin "1") (pinfunction "1_1") (pintype "passive"))
      (node (ref "D19") (pin "2") (pinfunction "K_2") (pintype "passive"))
      (node (ref "U2") (pin "13") (pinfunction "CHB_13") (pintype "passive"))
    )
    (net (code "48") (name "Net-(D20-A)") (class "Default")
      (node (ref "D20") (pin "1") (pinfunction "A_1") (pintype "passive"))
      (node (ref "Q12") (pin "1") (pinfunction "1_1") (pintype "passive"))
      (node (ref "R29") (pin "2") (pinfunction "2_2") (pintype "passive"))
    )
    (net (code "49") (name "Net-(D21-A)") (class "Default")
      (node (ref "D21") (pin "1") (pinfunction "A_1") (pintype "passive"))
      (node (ref "Q6") (pin "1") (pinfunction "1_1") (pintype "passive"))
      (node (ref "R30") (pin "2") (pinfunction "2_2") (pintype "passive"))
    )
    (net (code "50") (name "Net-(DIR-A)") (class "Default")
      (node (ref "DIR") (pin "1") (pinfunction "A_1") (pintype "passive"))
      (node (ref "R33") (pin "1") (pinfunction "1_1") (pintype "passive"))
    )
    (net (code "51") (name "Net-(FAULT-A)") (class "Default")
      (node (ref "FAULT") (pin "1") (pinfunction "A_1") (pintype "passive"))
      (node (ref "R58") (pin "1") (pinfunction "1_1") (pintype "passive"))
    )
    (net (code "52") (name "Net-(FUSE-A)") (class "Default")
      (node (ref "F1") (pin "2") (pinfunction "2_2") (pintype "passive"))
      (node (ref "FUSE") (pin "1") (pinfunction "A_1") (pintype "passive"))
      (node (ref "P6") (pin "1") (pinfunction "1_1") (pintype "passive"))
    )
    (net (code "53") (name "Net-(FUSE-K)") (class "Default")
      (node (ref "FUSE") (pin "2") (pinfunction "K_2") (pintype "passive"))
      (node (ref "R41") (pin "2") (pinfunction "2_2") (pintype "passive"))
    )
    (net (code "54") (name "Net-(PWM-A)") (class "Default")
      (node (ref "PWM") (pin "1") (pinfunction "A_1") (pintype "passive"))
      (node (ref "R32") (pin "1") (pinfunction "1_1") (pintype "passive"))
    )
    (net (code "55") (name "Net-(U1-ISENSE+)") (class "Default")
      (node (ref "C8") (pin "1") (pinfunction "1_1") (pintype "passive"))
      (node (ref "R20") (pin "2") (pinfunction "2_2") (pintype "passive"))
      (node (ref "U1") (pin "9") (pinfunction "ISENSE+_9") (pintype "passive"))
    )
    (net (code "56") (name "Net-(U1-OSC)") (class "Default")
      (node (ref "C9") (pin "1") (pinfunction "1_1") (pintype "passive"))
      (node (ref "R21") (pin "2") (pinfunction "2_2") (pintype "passive"))
      (node (ref "U1") (pin "10") (pinfunction "OSC_10") (pintype "passive"))
    )
    (net (code "57") (name "Net-(U2-AHS)") (class "Default")
      (node (ref "C4") (pin "2") (pinfunction "2_2") (pintype "passive"))
      (node (ref "R61") (pin "1") (pinfunction "1_1") (pintype "passive"))
      (node (ref "U2") (pin "18") (pinfunction "AHS_18") (pintype "passive"))
    )
    (net (code "58") (name "Net-(U2-BHS)") (class "Default")
      (node (ref "C7") (pin "2") (pinfunction "2_2") (pintype "passive"))
      (node (ref "R60") (pin "1") (pinfunction "1_1") (pintype "passive"))
      (node (ref "U2") (pin "23") (pinfunction "BHS_23") (pintype "passive"))
    )
    (net (code "59") (name "Net-(U2-CHS)") (class "Default")
      (node (ref "C17") (pin "2") (pinfunction "2_2") (pintype "passive"))
      (node (ref "R59") (pin "1") (pinfunction "1_1") (pintype "passive"))
      (node (ref "U2") (pin "15") (pinfunction "CHS_15") (pintype "passive"))
    )
    (net (code "60") (name "Net-(U2-RDEL)") (class "Default")
      (node (ref "R28") (pin "1") (pinfunction "1_1") (pintype "passive"))
      (node (ref "U2") (pin "7") (pinfunction "RDEL_7") (pintype "passive"))
    )
    (net (code "61") (name "Net-(U4-C1+)") (class "Default")
      (node (ref "C12") (pin "2") (pinfunction "2_2") (pintype "passive"))
      (node (ref "U4") (pin "2") (pinfunction "C1+_2") (pintype "passive"))
    )
    (net (code "62") (name "Net-(U4-C1-)") (class "Default")
      (node (ref "C12") (pin "1") (pinfunction "1_1") (pintype "passive"))
      (node (ref "U4") (pin "1") (pinfunction "C1-_1") (pintype "passive"))
    )
    (net (code "63") (name "Net-(U4-C2+)") (class "Default")
      (node (ref "C14") (pin "2") (pinfunction "2_2") (pintype "passive"))
      (node (ref "U4") (pin "4") (pinfunction "C2+_4") (pintype "power_in"))
    )
    (net (code "64") (name "Net-(U4-C2-)") (class "Default")
      (node (ref "C14") (pin "1") (pinfunction "1_1") (pintype "passive"))
      (node (ref "U4") (pin "3") (pinfunction "C2-_3") (pintype "passive"))
    )
    (net (code "65") (name "Net-(U5-C1+)") (class "Default")
      (node (ref "C20") (pin "2") (pinfunction "2_2") (pintype "passive"))
      (node (ref "U5") (pin "2") (pinfunction "C1+_2") (pintype "passive"))
    )
    (net (code "66") (name "Net-(U5-C1-)") (class "Default")
      (node (ref "C20") (pin "1") (pinfunction "1_1") (pintype "passive"))
      (node (ref "U5") (pin "1") (pinfunction "C1-_1") (pintype "passive"))
    )
    (net (code "67") (name "Net-(U5-C2+)") (class "Default")
      (node (ref "C22") (pin "2") (pinfunction "2_2") (pintype "passive"))
      (node (ref "U5") (pin "4") (pinfunction "C2+_4") (pintype "power_in"))
    )
    (net (code "68") (name "Net-(U5-C2-)") (class "Default")
      (node (ref "C22") (pin "1") (pinfunction "1_1") (pintype "passive"))
      (node (ref "U5") (pin "3") (pinfunction "C2-_3") (pintype "passive"))
    )
    (net (code "69") (name "VCC_5V") (class "Default")
      (node (ref "5V") (pin "1") (pinfunction "A_1") (pintype "passive"))
      (node (ref "C15") (pin "1") (pinfunction "1_1") (pintype "passive"))
      (node (ref "C16") (pin "1") (pinfunction "1_1") (pintype "passive"))
      (node (ref "C18") (pin "1") (pinfunction "1_1") (pintype "passive"))
      (node (ref "C23") (pin "1") (pinfunction "1_1") (pintype "passive"))
      (node (ref "P4") (pin "2") (pinfunction "2_2") (pintype "passive"))
      (node (ref "P5") (pin "1") (pinfunction "1_1") (pintype "passive"))
      (node (ref "R12") (pin "2") (pinfunction "2_2") (pintype "passive"))
      (node (ref "R13") (pin "2") (pinfunction "2_2") (pintype "passive"))
      (node (ref "R18") (pin "2") (pinfunction "2_2") (pintype "passive"))
      (node (ref "R22") (pin "2") (pinfunction "2_2") (pintype "passive"))
      (node (ref "R3") (pin "2") (pinfunction "2_2") (pintype "passive"))
      (node (ref "R5") (pin "2") (pinfunction "2_2") (pintype "passive"))
      (node (ref "R52") (pin "2") (pinfunction "2_2") (pintype "passive"))
      (node (ref "R53") (pin "2") (pinfunction "2_2") (pintype "passive"))
      (node (ref "R54") (pin "2") (pinfunction "2_2") (pintype "passive"))
      (node (ref "R55") (pin "2") (pinfunction "2_2") (pintype "passive"))
      (node (ref "U1") (pin "7") (pinfunction "OE_7") (pintype "passive"))
      (node (ref "U3") (pin "14") (pinfunction "VCC_14") (pintype "power_in"))
      (node (ref "U3") (pin "2") (pinfunction "1A_2") (pintype "input"))
      (node (ref "U3") (pin "3") (pinfunction "1B_3") (pintype "input"))
      (node (ref "U4") (pin "5") (pinfunction "VCC_5") (pintype "passive"))
      (node (ref "U5") (pin "5") (pinfunction "VCC_5") (pintype "passive"))
    )
    (net (code "70") (name "VCC_12V") (class "Default")
      (node (ref "12V") (pin "1") (pinfunction "A_1") (pintype "passive"))
      (node (ref "C10") (pin "1") (pinfunction "1_1") (pintype "passive"))
      (node (ref "C11") (pin "1") (pinfunction "1_1") (pintype "passive"))
      (node (ref "C13") (pin "1") (pinfunction "1_1") (pintype "passive"))
      (node (ref "C19") (pin "1") (pinfunction "1_1") (pintype "passive"))
      (node (ref "C21") (pin "1") (pinfunction "1_1") (pintype "passive"))
      (node (ref "D12") (pin "1") (pinfunction "A_1") (pintype "passive"))
      (node (ref "D19") (pin "1") (pinfunction "A_1") (pintype "passive"))
      (node (ref "D5") (pin "1") (pinfunction "A_1") (pintype "passive"))
      (node (ref "R28") (pin "2") (pinfunction "2_2") (pintype "passive"))
      (node (ref "U1") (pin "17") (pinfunction "VCC_17") (pintype "passive"))
      (node (ref "U1") (pin "18") (pinfunction "VLOGIC_18") (pintype "passive"))
      (node (ref "U2") (pin "20") (pinfunction "VCC_20") (pintype "passive"))
      (node (ref "U4") (pin "6") (pinfunction "VOUT_6") (pintype "passive"))
      (node (ref "U5") (pin "6") (pinfunction "VOUT_6") (pintype "passive"))
    )
    (net (code "71") (name "VCC_24V") (class "Default")
      (node (ref "C25") (pin "1") (pinfunction "1_1") (pintype "passive"))
      (node (ref "C29") (pin "2") (pinfunction "2_2") (pintype "passive"))
      (node (ref "C30") (pin "2") (pinfunction "2_2") (pintype "passive"))
      (node (ref "C31") (pin "2") (pinfunction "2_2") (pintype "passive"))
      (node (ref "F1") (pin "1") (pinfunction "1_1") (pintype "passive"))
      (node (ref "Q1") (pin "2") (pinfunction "D_2") (pintype "passive"))
      (node (ref "Q11") (pin "2") (pinfunction "D_2") (pintype "passive"))
      (node (ref "Q3") (pin "2") (pinfunction "D_2") (pintype "passive"))
      (node (ref "Q5") (pin "2") (pinfunction "D_2") (pintype "passive"))
      (node (ref "Q7") (pin "2") (pinfunction "D_2") (pintype "passive"))
      (node (ref "Q9") (pin "2") (pinfunction "D_2") (pintype "passive"))
      (node (ref "R41") (pin "1") (pinfunction "1_1") (pintype "passive"))
    )
    (net (code "72") (name "VCC_REF") (class "Default")
      (node (ref "R21") (pin "1") (pinfunction "1_1") (pintype "passive"))
      (node (ref "U1") (pin "8") (pinfunction "VREFOUT_8") (pintype "passive"))
    )
    (net (code "73") (name "unconnected-(U1-ERROUT{slash}PWM--Pad13)") (class "Default")
      (node (ref "U1") (pin "13") (pinfunction "ERROUT/PWM-_13") (pintype "passive"))
    )
    (net (code "74") (name "unconnected-(U2-RFSH-Pad9)") (class "Default")
      (node (ref "U2") (pin "9") (pinfunction "RFSH_9") (pintype "passive+no_connect"))
    )
    (net (code "75") (name "unconnected-(U2-UVLO-Pad8)") (class "Default")
      (node (ref "U2") (pin "8") (pinfunction "UVLO_8") (pintype "passive+no_connect"))
    )
    (net (code "76") (name "unconnected-(U3A-1Y-Pad1)") (class "Default")
      (node (ref "U3") (pin "1") (pinfunction "1Y_1") (pintype "output"))
    )
  )
)
